# QRsch_v2_0.net
KiCad netlist of a schematic drawn in EAGLE
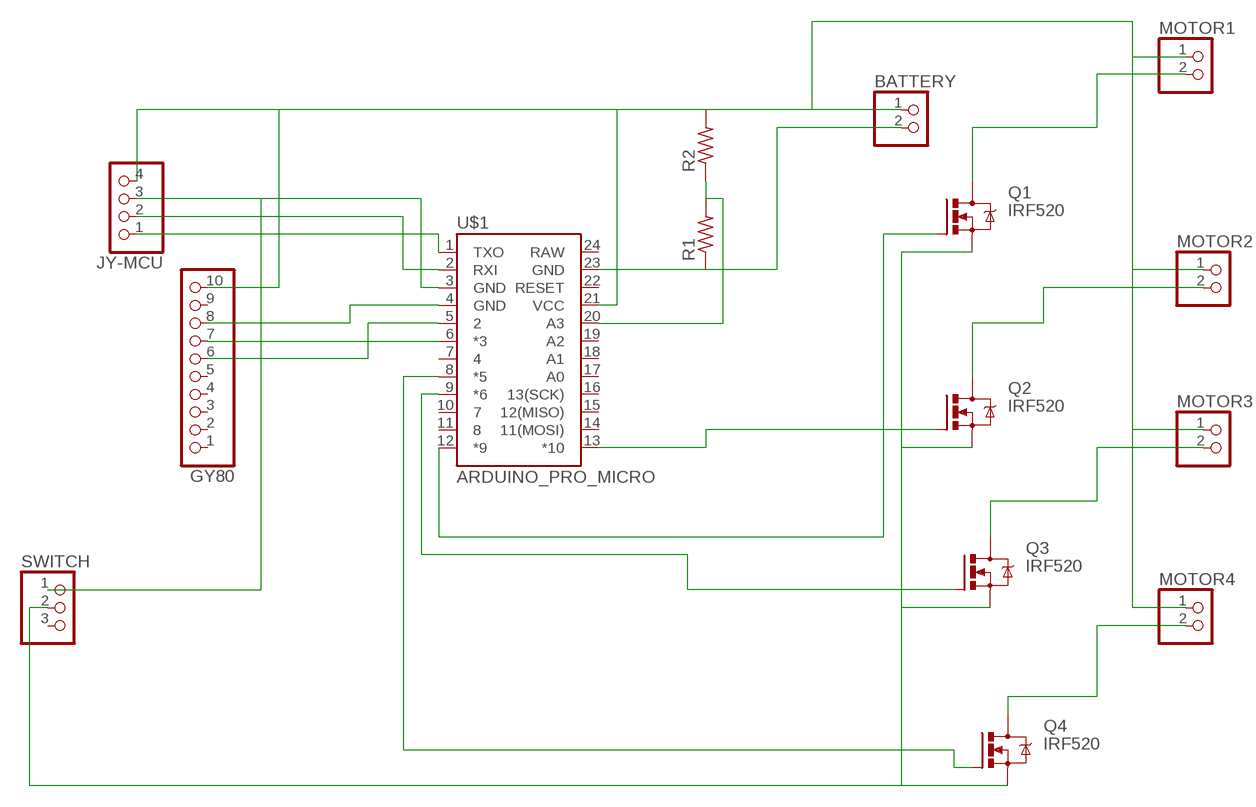
[diagram p0: schematic, sheet 1]

(export (version "E")
  (design (tool "Eeschema 10.0.6"))
  (components
    (comp (ref "BATTERY")
      (value "PINHD-1X2/90")
      (footprint "eagle-import:1X02_90")
      (libsource (lib "eagle-import") (part "PINHD-1X2/90"))
    )
    (comp (ref "GY80")
      (value "PINHD-1X10")
      (footprint "eagle-import:1X10")
      (libsource (lib "eagle-import") (part "PINHD-1X10"))
    )
    (comp (ref "JY-MCU")
      (value "PINHD-1X4")
      (footprint "eagle-import:1X04")
      (libsource (lib "eagle-import") (part "PINHD-1X4"))
    )
    (comp (ref "MOTOR1")
      (value "PINHD-1X2/90")
      (footprint "eagle-import:1X02_90")
      (libsource (lib "eagle-import") (part "PINHD-1X2/90"))
    )
    (comp (ref "MOTOR2")
      (value "PINHD-1X2/90")
      (footprint "eagle-import:1X02_90")
      (libsource (lib "eagle-import") (part "PINHD-1X2/90"))
    )
    (comp (ref "MOTOR3")
      (value "PINHD-1X2/90")
      (footprint "eagle-import:1X02_90")
      (libsource (lib "eagle-import") (part "PINHD-1X2/90"))
    )
    (comp (ref "MOTOR4")
      (value "PINHD-1X2/90")
      (footprint "eagle-import:1X02_90")
      (libsource (lib "eagle-import") (part "PINHD-1X2/90"))
    )
    (comp (ref "Q1")
      (value "IRF520")
      (footprint "eagle-import:TO220BV")
      (libsource (lib "eagle-import") (part "IRF520"))
    )
    (comp (ref "Q2")
      (value "IRF520")
      (footprint "eagle-import:TO220BV")
      (libsource (lib "eagle-import") (part "IRF520"))
    )
    (comp (ref "Q3")
      (value "IRF520")
      (footprint "eagle-import:TO220BV")
      (libsource (lib "eagle-import") (part "IRF520"))
    )
    (comp (ref "Q4")
      (value "IRF520")
      (footprint "eagle-import:TO220BV")
      (libsource (lib "eagle-import") (part "IRF520"))
    )
    (comp (ref "R1")
      (value "R-US_0207/7")
      (footprint "eagle-import:0207_7")
      (libsource (lib "eagle-import") (part "R-US_0207/7"))
    )
    (comp (ref "R2")
      (value "R-US_0207/7")
      (footprint "eagle-import:0207_7")
      (libsource (lib "eagle-import") (part "R-US_0207/7"))
    )
    (comp (ref "SWITCH")
      (value "PINHD-1X3")
      (footprint "eagle-import:1X03")
      (libsource (lib "eagle-import") (part "PINHD-1X3"))
    )
    (comp (ref "U$1")
      (value "ARDUINO_PRO_MICRO")
      (footprint "eagle-import:ARDUINO_PRO_MICRO")
      (libsource (lib "eagle-import") (part "ARDUINO_PRO_MICRO"))
    )
  )
  (nets
    (net (code "1") (name "/GND") (class "Default")
      (node (ref "BATTERY") (pin "2") (pinfunction "2_2") (pintype "passive"))
      (node (ref "GY80") (pin "8") (pinfunction "8_8") (pintype "passive"))
      (node (ref "JY-MCU") (pin "3") (pinfunction "3_3") (pintype "passive"))
      (node (ref "R1") (pin "1") (pinfunction "1_1") (pintype "passive"))
      (node (ref "SWITCH") (pin "1") (pinfunction "1_1") (pintype "passive"))
      (node (ref "U$1") (pin "23") (pinfunction "GND_23") (pintype "bidirectional"))
      (node (ref "U$1") (pin "3") (pinfunction "GND_3") (pintype "bidirectional"))
      (node (ref "U$1") (pin "4") (pinfunction "GND_4") (pintype "bidirectional"))
    )
    (net (code "2") (name "Net-(MOTOR1-Pad2)") (class "Default")
      (node (ref "MOTOR1") (pin "2") (pinfunction "2_2") (pintype "passive"))
      (node (ref "Q1") (pin "D") (pinfunction "D_D") (pintype "passive"))
    )
    (net (code "3") (name "Net-(MOTOR2-Pad2)") (class "Default")
      (node (ref "MOTOR2") (pin "2") (pinfunction "2_2") (pintype "passive"))
      (node (ref "Q2") (pin "D") (pinfunction "D_D") (pintype "passive"))
    )
    (net (code "4") (name "Net-(MOTOR3-Pad2)") (class "Default")
      (node (ref "MOTOR3") (pin "2") (pinfunction "2_2") (pintype "passive"))
      (node (ref "Q3") (pin "D") (pinfunction "D_D") (pintype "passive"))
    )
    (net (code "5") (name "Net-(MOTOR4-Pad2)") (class "Default")
      (node (ref "MOTOR4") (pin "2") (pinfunction "2_2") (pintype "passive"))
      (node (ref "Q4") (pin "D") (pinfunction "D_D") (pintype "passive"))
    )
    (net (code "6") (name "Net-(Q1-PadS)") (class "Default")
      (node (ref "Q1") (pin "S") (pinfunction "S_S") (pintype "passive"))
      (node (ref "Q2") (pin "S") (pinfunction "S_S") (pintype "passive"))
      (node (ref "Q3") (pin "S") (pinfunction "S_S") (pintype "passive"))
      (node (ref "Q4") (pin "S") (pinfunction "S_S") (pintype "passive"))
      (node (ref "SWITCH") (pin "2") (pinfunction "2_2") (pintype "passive"))
    )
    (net (code "7") (name "Net-(U$1-*3)") (class "Default")
      (node (ref "GY80") (pin "7") (pinfunction "7_7") (pintype "passive"))
      (node (ref "U$1") (pin "6") (pinfunction "*3_6") (pintype "bidirectional"))
    )
    (net (code "8") (name "Net-(U$1-*5)") (class "Default")
      (node (ref "Q4") (pin "G") (pinfunction "G_G") (pintype "passive"))
      (node (ref "U$1") (pin "8") (pinfunction "*5_8") (pintype "bidirectional"))
    )
    (net (code "9") (name "Net-(U$1-*6)") (class "Default")
      (node (ref "Q3") (pin "G") (pinfunction "G_G") (pintype "passive"))
      (node (ref "U$1") (pin "9") (pinfunction "*6_9") (pintype "bidirectional"))
    )
    (net (code "10") (name "Net-(U$1-*9)") (class "Default")
      (node (ref "Q1") (pin "G") (pinfunction "G_G") (pintype "passive"))
      (node (ref "U$1") (pin "12") (pinfunction "*9_12") (pintype "bidirectional"))
    )
    (net (code "11") (name "Net-(U$1-*10)") (class "Default")
      (node (ref "Q2") (pin "G") (pinfunction "G_G") (pintype "passive"))
      (node (ref "U$1") (pin "13") (pinfunction "*10_13") (pintype "bidirectional"))
    )
    (net (code "12") (name "Net-(U$1-2)") (class "Default")
      (node (ref "GY80") (pin "6") (pinfunction "6_6") (pintype "passive"))
      (node (ref "U$1") (pin "5") (pinfunction "2_5") (pintype "bidirectional"))
    )
    (net (code "13") (name "Net-(U$1-A3)") (class "Default")
      (node (ref "R1") (pin "2") (pinfunction "2_2") (pintype "passive"))
      (node (ref "R2") (pin "1") (pinfunction "1_1") (pintype "passive"))
      (node (ref "U$1") (pin "20") (pinfunction "A3_20") (pintype "bidirectional"))
    )
    (net (code "14") (name "Net-(U$1-RXI)") (class "Default")
      (node (ref "JY-MCU") (pin "2") (pinfunction "2_2") (pintype "passive"))
      (node (ref "U$1") (pin "2") (pinfunction "RXI_2") (pintype "bidirectional"))
    )
    (net (code "15") (name "Net-(U$1-TXO)") (class "Default")
      (node (ref "JY-MCU") (pin "1") (pinfunction "1_1") (pintype "passive"))
      (node (ref "U$1") (pin "1") (pinfunction "TXO_1") (pintype "bidirectional"))
    )
    (net (code "16") (name "Net-(U$1-VCC)") (class "Default")
      (node (ref "BATTERY") (pin "1") (pinfunction "1_1") (pintype "passive"))
      (node (ref "GY80") (pin "10") (pinfunction "10_10") (pintype "passive"))
      (node (ref "JY-MCU") (pin "4") (pinfunction "4_4") (pintype "passive"))
      (node (ref "MOTOR1") (pin "1") (pinfunction "1_1") (pintype "passive"))
      (node (ref "MOTOR2") (pin "1") (pinfunction "1_1") (pintype "passive"))
      (node (ref "MOTOR3") (pin "1") (pinfunction "1_1") (pintype "passive"))
      (node (ref "MOTOR4") (pin "1") (pinfunction "1_1") (pintype "passive"))
      (node (ref "R2") (pin "2") (pinfunction "2_2") (pintype "passive"))
      (node (ref "U$1") (pin "21") (pinfunction "VCC_21") (pintype "bidirectional"))
    )
    (net (code "17") (name "unconnected-(GY80-Pad1)") (class "Default")
      (node (ref "GY80") (pin "1") (pinfunction "1_1") (pintype "passive"))
    )
    (net (code "18") (name "unconnected-(GY80-Pad2)") (class "Default")
      (node (ref "GY80") (pin "2") (pinfunction "2_2") (pintype "passive"))
    )
    (net (code "19") (name "unconnected-(GY80-Pad3)") (class "Default")
      (node (ref "GY80") (pin "3") (pinfunction "3_3") (pintype "passive"))
    )
    (net (code "20") (name "unconnected-(GY80-Pad4)") (class "Default")
      (node (ref "GY80") (pin "4") (pinfunction "4_4") (pintype "passive"))
    )
    (net (code "21") (name "unconnected-(GY80-Pad5)") (class "Default")
      (node (ref "GY80") (pin "5") (pinfunction "5_5") (pintype "passive"))
    )
    (net (code "22") (name "unconnected-(GY80-Pad9)") (class "Default")
      (node (ref "GY80") (pin "9") (pinfunction "9_9") (pintype "passive"))
    )
    (net (code "23") (name "unconnected-(SWITCH-Pad3)") (class "Default")
      (node (ref "SWITCH") (pin "3") (pinfunction "3_3") (pintype "passive"))
    )
    (net (code "24") (name "unconnected-(U$1-4-Pad7)") (class "Default")
      (node (ref "U$1") (pin "7") (pinfunction "4_7") (pintype "bidirectional"))
    )
    (net (code "25") (name "unconnected-(U$1-7-Pad10)") (class "Default")
      (node (ref "U$1") (pin "10") (pinfunction "7_10") (pintype "bidirectional"))
    )
    (net (code "26") (name "unconnected-(U$1-8-Pad11)") (class "Default")
      (node (ref "U$1") (pin "11") (pinfunction "8_11") (pintype "bidirectional"))
    )
    (net (code "27") (name "unconnected-(U$1-11(MOSI)-Pad14)") (class "Default")
      (node (ref "U$1") (pin "14") (pinfunction "11(MOSI)_14") (pintype "bidirectional"))
    )
    (net (code "28") (name "unconnected-(U$1-12(MISO)-Pad15)") (class "Default")
      (node (ref "U$1") (pin "15") (pinfunction "12(MISO)_15") (pintype "bidirectional"))
    )
    (net (code "29") (name "unconnected-(U$1-13(SCK)-Pad16)") (class "Default")
      (node (ref "U$1") (pin "16") (pinfunction "13(SCK)_16") (pintype "bidirectional"))
    )
    (net (code "30") (name "unconnected-(U$1-A0-Pad17)") (class "Default")
      (node (ref "U$1") (pin "17") (pinfunction "A0_17") (pintype "bidirectional"))
    )
    (net (code "31") (name "unconnected-(U$1-A1-Pad18)") (class "Default")
      (node (ref "U$1") (pin "18") (pinfunction "A1_18") (pintype "bidirectional"))
    )
    (net (code "32") (name "unconnected-(U$1-A2-Pad19)") (class "Default")
      (node (ref "U$1") (pin "19") (pinfunction "A2_19") (pintype "bidirectional"))
    )
    (net (code "33") (name "unconnected-(U$1-RAW-Pad24)") (class "Default")
      (node (ref "U$1") (pin "24") (pinfunction "RAW_24") (pintype "bidirectional"))
    )
    (net (code "34") (name "unconnected-(U$1-RESET-Pad22)") (class "Default")
      (node (ref "U$1") (pin "22") (pinfunction "RESET_22") (pintype "bidirectional"))
    )
  )
)
